# hbb-v0.net
KiCad netlist of a schematic drawn in EAGLE
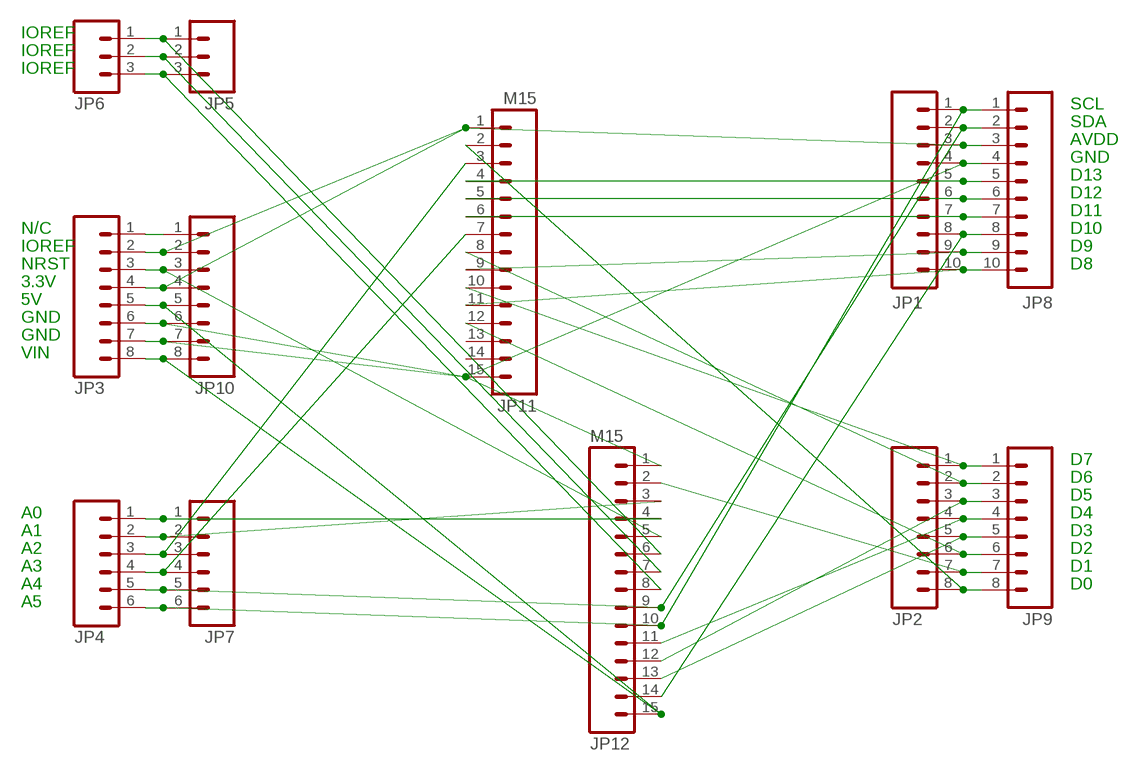
[diagram p0: schematic, sheet 1]

(export (version "E")
  (design (tool "Eeschema 10.0.6"))
  (components
    (comp (ref "JP1")
      (value "M10NO_SILK_PTH_FEMALE")
      (footprint "eagle-import:1X10_NO_SILK")
      (libsource (lib "eagle-import") (part "M10NO_SILK_PTH_FEMALE"))
    )
    (comp (ref "JP2")
      (value "M08NO_SILK_FEMALE_PTH")
      (footprint "eagle-import:1X08_NO_SILK")
      (libsource (lib "eagle-import") (part "M08NO_SILK_FEMALE_PTH"))
    )
    (comp (ref "JP3")
      (value "M08NO_SILK_FEMALE_PTH")
      (footprint "eagle-import:1X08_NO_SILK")
      (libsource (lib "eagle-import") (part "M08NO_SILK_FEMALE_PTH"))
    )
    (comp (ref "JP4")
      (value "M06NO_SILK_FEMALE_PTH")
      (footprint "eagle-import:1X06_NO_SILK")
      (libsource (lib "eagle-import") (part "M06NO_SILK_FEMALE_PTH"))
    )
    (comp (ref "JP5")
      (value "M03LOCK_NO_SILK")
      (footprint "eagle-import:1X03_LOCK_NO_SILK")
      (libsource (lib "eagle-import") (part "M03LOCK_NO_SILK"))
    )
    (comp (ref "JP6")
      (value "M03PTH")
      (footprint "eagle-import:1X03")
      (libsource (lib "eagle-import") (part "M03PTH"))
    )
    (comp (ref "JP7")
      (value "M06NO_SILK_FEMALE_PTH")
      (footprint "eagle-import:1X06_NO_SILK")
      (libsource (lib "eagle-import") (part "M06NO_SILK_FEMALE_PTH"))
    )
    (comp (ref "JP8")
      (value "M10NO_SILK_PTH_FEMALE")
      (footprint "eagle-import:1X10_NO_SILK")
      (libsource (lib "eagle-import") (part "M10NO_SILK_PTH_FEMALE"))
    )
    (comp (ref "JP9")
      (value "M08NO_SILK_FEMALE_PTH")
      (footprint "eagle-import:1X08_NO_SILK")
      (libsource (lib "eagle-import") (part "M08NO_SILK_FEMALE_PTH"))
    )
    (comp (ref "JP10")
      (value "M08NO_SILK_FEMALE_PTH")
      (footprint "eagle-import:1X08_NO_SILK")
      (libsource (lib "eagle-import") (part "M08NO_SILK_FEMALE_PTH"))
    )
    (comp (ref "JP11")
      (value "M15")
      (footprint "eagle-import:1X15")
      (libsource (lib "eagle-import") (part "M15"))
    )
    (comp (ref "JP12")
      (value "M15")
      (footprint "eagle-import:1X15")
      (libsource (lib "eagle-import") (part "M15"))
    )
  )
  (nets
    (net (code "1") (name "Net-(JP1-Pad1)") (class "Default")
      (node (ref "JP1") (pin "1") (pinfunction "1_1") (pintype "passive"))
      (node (ref "JP12") (pin "10") (pinfunction "10_10") (pintype "passive"))
      (node (ref "JP4") (pin "6") (pinfunction "6_6") (pintype "passive"))
      (node (ref "JP7") (pin "6") (pinfunction "6_6") (pintype "passive"))
      (node (ref "JP8") (pin "1") (pinfunction "1_1") (pintype "passive"))
    )
    (net (code "2") (name "Net-(JP1-Pad2)") (class "Default")
      (node (ref "JP1") (pin "2") (pinfunction "2_2") (pintype "passive"))
      (node (ref "JP12") (pin "9") (pinfunction "9_9") (pintype "passive"))
      (node (ref "JP4") (pin "5") (pinfunction "5_5") (pintype "passive"))
      (node (ref "JP7") (pin "5") (pinfunction "5_5") (pintype "passive"))
      (node (ref "JP8") (pin "2") (pinfunction "2_2") (pintype "passive"))
    )
    (net (code "3") (name "Net-(JP1-Pad3)") (class "Default")
      (node (ref "JP1") (pin "3") (pinfunction "3_3") (pintype "passive"))
      (node (ref "JP10") (pin "2") (pinfunction "2_2") (pintype "passive"))
      (node (ref "JP10") (pin "4") (pinfunction "4_4") (pintype "passive"))
      (node (ref "JP11") (pin "1") (pinfunction "1_1") (pintype "passive"))
      (node (ref "JP3") (pin "2") (pinfunction "2_2") (pintype "passive"))
      (node (ref "JP3") (pin "4") (pinfunction "4_4") (pintype "passive"))
      (node (ref "JP8") (pin "3") (pinfunction "3_3") (pintype "passive"))
    )
    (net (code "4") (name "Net-(JP1-Pad4)") (class "Default")
      (node (ref "JP1") (pin "4") (pinfunction "4_4") (pintype "passive"))
      (node (ref "JP10") (pin "6") (pinfunction "6_6") (pintype "passive"))
      (node (ref "JP10") (pin "7") (pinfunction "7_7") (pintype "passive"))
      (node (ref "JP11") (pin "15") (pinfunction "15_15") (pintype "passive"))
      (node (ref "JP12") (pin "1") (pinfunction "1_1") (pintype "passive"))
      (node (ref "JP3") (pin "6") (pinfunction "6_6") (pintype "passive"))
      (node (ref "JP3") (pin "7") (pinfunction "7_7") (pintype "passive"))
      (node (ref "JP8") (pin "4") (pinfunction "4_4") (pintype "passive"))
    )
    (net (code "5") (name "Net-(JP1-Pad5)") (class "Default")
      (node (ref "JP1") (pin "5") (pinfunction "5_5") (pintype "passive"))
      (node (ref "JP11") (pin "4") (pinfunction "4_4") (pintype "passive"))
      (node (ref "JP8") (pin "5") (pinfunction "5_5") (pintype "passive"))
    )
    (net (code "6") (name "Net-(JP1-Pad6)") (class "Default")
      (node (ref "JP1") (pin "6") (pinfunction "6_6") (pintype "passive"))
      (node (ref "JP11") (pin "5") (pinfunction "5_5") (pintype "passive"))
      (node (ref "JP8") (pin "6") (pinfunction "6_6") (pintype "passive"))
    )
    (net (code "7") (name "Net-(JP1-Pad7)") (class "Default")
      (node (ref "JP1") (pin "7") (pinfunction "7_7") (pintype "passive"))
      (node (ref "JP11") (pin "6") (pinfunction "6_6") (pintype "passive"))
      (node (ref "JP8") (pin "7") (pinfunction "7_7") (pintype "passive"))
    )
    (net (code "8") (name "Net-(JP1-Pad8)") (class "Default")
      (node (ref "JP1") (pin "8") (pinfunction "8_8") (pintype "passive"))
      (node (ref "JP12") (pin "14") (pinfunction "14_14") (pintype "passive"))
      (node (ref "JP8") (pin "8") (pinfunction "8_8") (pintype "passive"))
    )
    (net (code "9") (name "Net-(JP1-Pad9)") (class "Default")
      (node (ref "JP1") (pin "9") (pinfunction "9_9") (pintype "passive"))
      (node (ref "JP11") (pin "9") (pinfunction "9_9") (pintype "passive"))
      (node (ref "JP8") (pin "9") (pinfunction "9_9") (pintype "passive"))
    )
    (net (code "10") (name "Net-(JP1-Pad10)") (class "Default")
      (node (ref "JP1") (pin "10") (pinfunction "10_10") (pintype "passive"))
      (node (ref "JP11") (pin "11") (pinfunction "11_11") (pintype "passive"))
      (node (ref "JP8") (pin "10") (pinfunction "10_10") (pintype "passive"))
    )
    (net (code "11") (name "Net-(JP10-Pad1)") (class "Default")
      (node (ref "JP10") (pin "1") (pinfunction "1_1") (pintype "passive"))
      (node (ref "JP3") (pin "1") (pinfunction "1_1") (pintype "passive"))
    )
    (net (code "12") (name "Net-(JP10-Pad3)") (class "Default")
      (node (ref "JP10") (pin "3") (pinfunction "3_3") (pintype "passive"))
      (node (ref "JP12") (pin "5") (pinfunction "5_5") (pintype "passive"))
      (node (ref "JP3") (pin "3") (pinfunction "3_3") (pintype "passive"))
    )
    (net (code "13") (name "Net-(JP10-Pad5)") (class "Default")
      (node (ref "JP10") (pin "5") (pinfunction "5_5") (pintype "passive"))
      (node (ref "JP10") (pin "8") (pinfunction "8_8") (pintype "passive"))
      (node (ref "JP12") (pin "15") (pinfunction "15_15") (pintype "passive"))
      (node (ref "JP3") (pin "5") (pinfunction "5_5") (pintype "passive"))
      (node (ref "JP3") (pin "8") (pinfunction "8_8") (pintype "passive"))
    )
    (net (code "14") (name "Net-(JP11-Pad2)") (class "Default")
      (node (ref "JP11") (pin "2") (pinfunction "2_2") (pintype "passive"))
      (node (ref "JP2") (pin "8") (pinfunction "8_8") (pintype "passive"))
      (node (ref "JP9") (pin "8") (pinfunction "8_8") (pintype "passive"))
    )
    (net (code "15") (name "Net-(JP11-Pad3)") (class "Default")
      (node (ref "JP11") (pin "3") (pinfunction "3_3") (pintype "passive"))
      (node (ref "JP4") (pin "3") (pinfunction "3_3") (pintype "passive"))
      (node (ref "JP7") (pin "3") (pinfunction "3_3") (pintype "passive"))
    )
    (net (code "16") (name "Net-(JP11-Pad7)") (class "Default")
      (node (ref "JP11") (pin "7") (pinfunction "7_7") (pintype "passive"))
      (node (ref "JP4") (pin "4") (pinfunction "4_4") (pintype "passive"))
      (node (ref "JP7") (pin "4") (pinfunction "4_4") (pintype "passive"))
    )
    (net (code "17") (name "Net-(JP11-Pad8)") (class "Default")
      (node (ref "JP11") (pin "8") (pinfunction "8_8") (pintype "passive"))
      (node (ref "JP2") (pin "2") (pinfunction "2_2") (pintype "passive"))
      (node (ref "JP9") (pin "2") (pinfunction "2_2") (pintype "passive"))
    )
    (net (code "18") (name "Net-(JP11-Pad10)") (class "Default")
      (node (ref "JP11") (pin "10") (pinfunction "10_10") (pintype "passive"))
      (node (ref "JP2") (pin "1") (pinfunction "1_1") (pintype "passive"))
      (node (ref "JP9") (pin "1") (pinfunction "1_1") (pintype "passive"))
    )
    (net (code "19") (name "Net-(JP11-Pad12)") (class "Default")
      (node (ref "JP11") (pin "12") (pinfunction "12_12") (pintype "passive"))
      (node (ref "JP2") (pin "6") (pinfunction "6_6") (pintype "passive"))
      (node (ref "JP9") (pin "6") (pinfunction "6_6") (pintype "passive"))
    )
    (net (code "20") (name "Net-(JP12-Pad2)") (class "Default")
      (node (ref "JP12") (pin "2") (pinfunction "2_2") (pintype "passive"))
      (node (ref "JP2") (pin "7") (pinfunction "7_7") (pintype "passive"))
      (node (ref "JP9") (pin "7") (pinfunction "7_7") (pintype "passive"))
    )
    (net (code "21") (name "Net-(JP12-Pad3)") (class "Default")
      (node (ref "JP12") (pin "3") (pinfunction "3_3") (pintype "passive"))
      (node (ref "JP4") (pin "2") (pinfunction "2_2") (pintype "passive"))
      (node (ref "JP7") (pin "2") (pinfunction "2_2") (pintype "passive"))
    )
    (net (code "22") (name "Net-(JP12-Pad4)") (class "Default")
      (node (ref "JP12") (pin "4") (pinfunction "4_4") (pintype "passive"))
      (node (ref "JP4") (pin "1") (pinfunction "1_1") (pintype "passive"))
      (node (ref "JP7") (pin "1") (pinfunction "1_1") (pintype "passive"))
    )
    (net (code "23") (name "Net-(JP12-Pad6)") (class "Default")
      (node (ref "JP12") (pin "6") (pinfunction "6_6") (pintype "passive"))
      (node (ref "JP5") (pin "1") (pinfunction "1_1") (pintype "passive"))
      (node (ref "JP6") (pin "1") (pinfunction "1_1") (pintype "passive"))
    )
    (net (code "24") (name "Net-(JP12-Pad7)") (class "Default")
      (node (ref "JP12") (pin "7") (pinfunction "7_7") (pintype "passive"))
      (node (ref "JP5") (pin "2") (pinfunction "2_2") (pintype "passive"))
      (node (ref "JP6") (pin "2") (pinfunction "2_2") (pintype "passive"))
    )
    (net (code "25") (name "Net-(JP12-Pad8)") (class "Default")
      (node (ref "JP12") (pin "8") (pinfunction "8_8") (pintype "passive"))
      (node (ref "JP5") (pin "3") (pinfunction "3_3") (pintype "passive"))
      (node (ref "JP6") (pin "3") (pinfunction "3_3") (pintype "passive"))
    )
    (net (code "26") (name "Net-(JP12-Pad11)") (class "Default")
      (node (ref "JP12") (pin "11") (pinfunction "11_11") (pintype "passive"))
      (node (ref "JP2") (pin "4") (pinfunction "4_4") (pintype "passive"))
      (node (ref "JP9") (pin "4") (pinfunction "4_4") (pintype "passive"))
    )
    (net (code "27") (name "Net-(JP12-Pad12)") (class "Default")
      (node (ref "JP12") (pin "12") (pinfunction "12_12") (pintype "passive"))
      (node (ref "JP2") (pin "3") (pinfunction "3_3") (pintype "passive"))
      (node (ref "JP9") (pin "3") (pinfunction "3_3") (pintype "passive"))
    )
    (net (code "28") (name "Net-(JP12-Pad13)") (class "Default")
      (node (ref "JP12") (pin "13") (pinfunction "13_13") (pintype "passive"))
      (node (ref "JP2") (pin "5") (pinfunction "5_5") (pintype "passive"))
      (node (ref "JP9") (pin "5") (pinfunction "5_5") (pintype "passive"))
    )
    (net (code "29") (name "unconnected-(JP11-Pad13)") (class "Default")
      (node (ref "JP11") (pin "13") (pinfunction "13_13") (pintype "passive"))
    )
    (net (code "30") (name "unconnected-(JP11-Pad14)") (class "Default")
      (node (ref "JP11") (pin "14") (pinfunction "14_14") (pintype "passive"))
    )
  )
)
